# lidar4_sch.net
KiCad netlist of a schematic drawn in Altium Designer
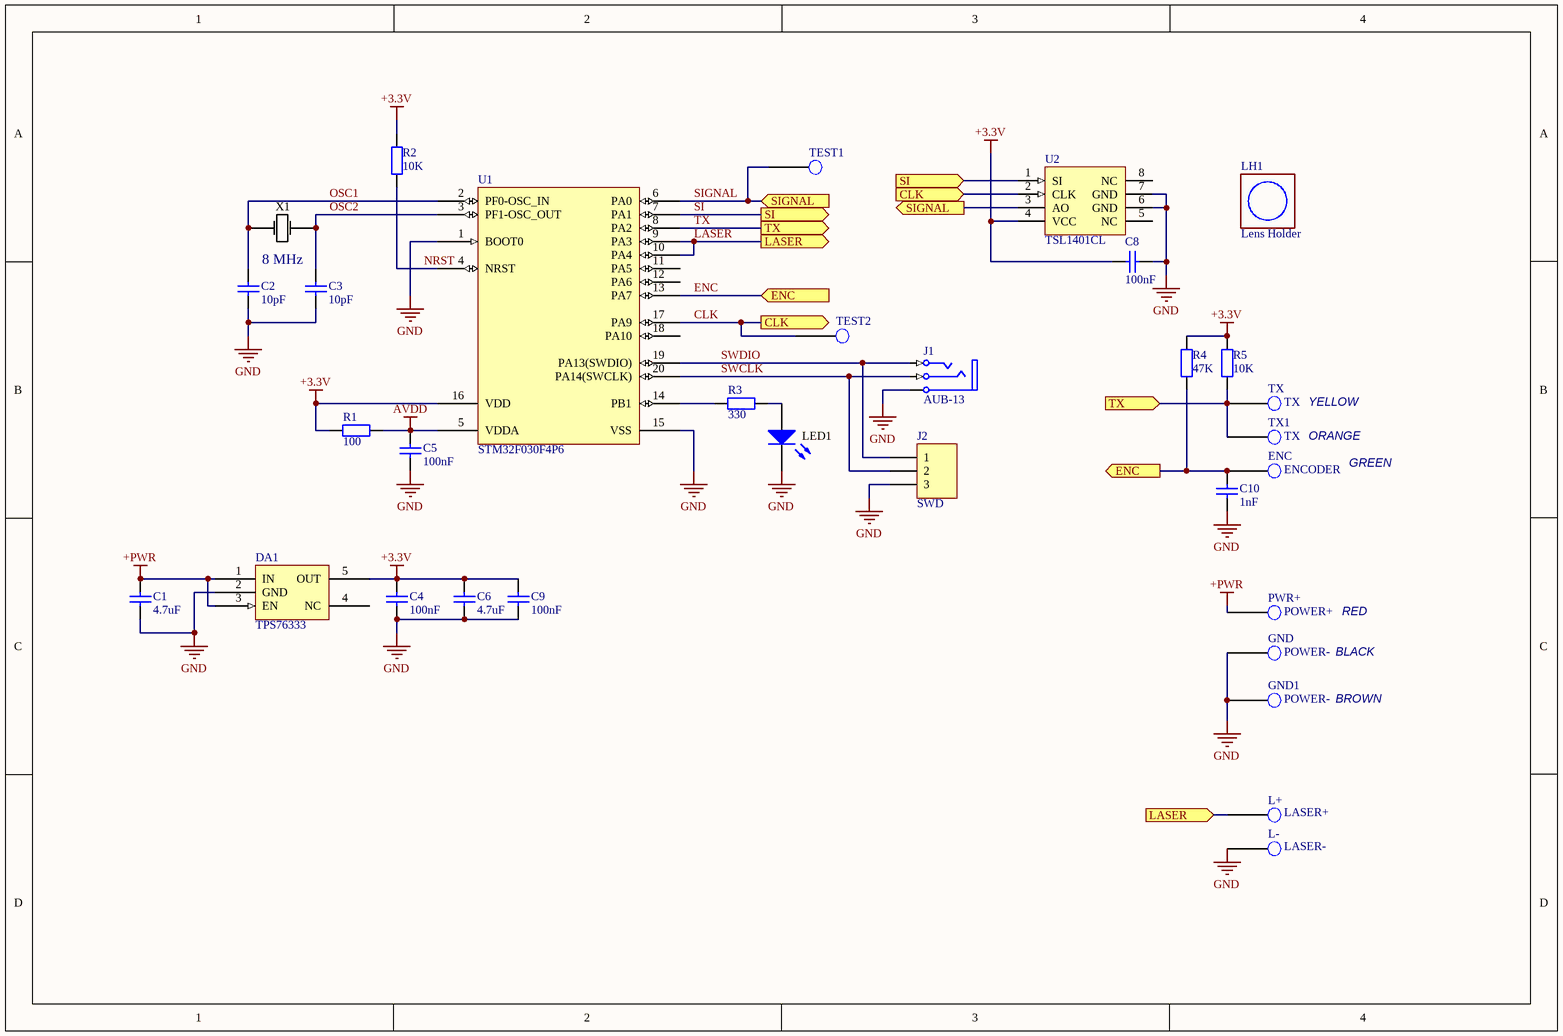
[diagram p0: lidar4_sch.SchDoc]

(export (version "E")
  (design (tool "Eeschema 10.0.6"))
  (components
    (comp (ref "C1")
      (value "4.7uF")
      (footprint "CAPC2012X135N")
      (description "Chip capacitor")
      (fields (field (name "VOLTAGE") "25V"))
      (libsource (lib "MyLibSch") (part "CC0805"))
    )
    (comp (ref "C2")
      (value "10pF")
      (footprint "CAPC1608X90N")
      (description "Chip capacitor")
      (fields (field (name "VOLTAGE") "25V"))
      (libsource (lib "MyLibSch") (part "CC0805"))
    )
    (comp (ref "C3")
      (value "10pF")
      (footprint "CAPC1608X90N")
      (description "Chip capacitor")
      (fields (field (name "VOLTAGE") "25V"))
      (libsource (lib "MyLibSch") (part "CC0805"))
    )
    (comp (ref "C4")
      (value "100nF")
      (footprint "CAPC1608X90N")
      (description "Chip capacitor")
      (fields (field (name "VOLTAGE") "25V"))
      (libsource (lib "MyLibSch") (part "CC0805"))
    )
    (comp (ref "C5")
      (value "100nF")
      (footprint "CAPC1608X90N")
      (description "Chip capacitor")
      (fields (field (name "VOLTAGE") "25V"))
      (libsource (lib "MyLibSch") (part "CC0805"))
    )
    (comp (ref "C6")
      (value "4.7uF")
      (footprint "CAPC2012X135N")
      (description "Chip capacitor")
      (fields (field (name "VOLTAGE") "25V"))
      (libsource (lib "MyLibSch") (part "CC0805"))
    )
    (comp (ref "C8")
      (value "100nF")
      (footprint "CAPC1608X90N")
      (description "Chip capacitor")
      (fields (field (name "VOLTAGE") "25V"))
      (libsource (lib "MyLibSch") (part "CC0805"))
    )
    (comp (ref "C9")
      (value "100nF")
      (footprint "CAPC1608X90N")
      (description "Chip capacitor")
      (fields (field (name "VOLTAGE") "25V"))
      (libsource (lib "MyLibSch") (part "CC0805"))
    )
    (comp (ref "C10")
      (value "1nF")
      (footprint "CAPC1608X90N")
      (description "Chip capacitor")
      (fields (field (name "VOLTAGE") "25V"))
      (libsource (lib "MyLibSch") (part "CC0805"))
    )
    (comp (ref "DA1")
      (value "TPS76333")
      (footprint "SOT23-5")
      (description "LDO")
      (libsource (lib "lcd_lib") (part "TPS76333"))
    )
    (comp (ref "ENC")
      (value "ENCODER")
      (footprint "Ext_hole")
      (description "Pad for wire")
      (libsource (lib "lcd_lib") (part "Ext Pad"))
    )
    (comp (ref "GND")
      (value "POWER-")
      (footprint "Ext_hole")
      (description "Pad for wire")
      (libsource (lib "lcd_lib") (part "Ext Pad"))
    )
    (comp (ref "GND1")
      (value "POWER-")
      (footprint "Ext_hole")
      (description "Pad for wire")
      (libsource (lib "lcd_lib") (part "Ext Pad"))
    )
    (comp (ref "J1")
      (value "AUB-13")
      (footprint "AUB-13")
      (description "Jack Socket, 1/4\" [6.5mm], Thru-Hole, Vertical, 3-Conductor Open Circuit (Non-Normalling)")
      (fields (field (name "PUBLISHER") "Altium Limited"))
      (libsource (lib "Miscellaneous Connectors") (part "Phonejack3"))
    )
    (comp (ref "J2")
      (value "SWD")
      (footprint "HDR1X3")
      (description "Header, 3-Pin")
      (fields (field (name "PUBLISHER") "Altium Limited"))
      (libsource (lib "Miscellaneous Connectors") (part "Header 3"))
    )
    (comp (ref "L+")
      (value "LASER+")
      (footprint "Ext_hole")
      (description "Pad for wire")
      (libsource (lib "lcd_lib") (part "Ext Pad"))
    )
    (comp (ref "L-")
      (value "LASER-")
      (footprint "Ext_hole")
      (description "Pad for wire")
      (libsource (lib "lcd_lib") (part "Ext Pad"))
    )
    (comp (ref "LED1")
      (value "LED")
      (footprint "PcbLib3:LED_0603")
      (description "LED_0603")
      (libsource (lib "lcd_lib") (part "LED_0603"))
    )
    (comp (ref "LH1")
      (value "Lens Holder")
      (footprint "LENS_HOLDER_2")
      (description "M12 Lens Holder")
      (libsource (lib "lcd_lib") (part "M12 Lens Holder"))
    )
    (comp (ref "PWR+")
      (value "POWER+")
      (footprint "Ext_hole")
      (description "Pad for wire")
      (libsource (lib "lcd_lib") (part "Ext Pad"))
    )
    (comp (ref "R1")
      (value "100")
      (footprint "RESC1608X55N")
      (description "Chip resistor")
      (fields (field (name "TOLERANCE") "5%"))
      (libsource (lib "") (part "RC0805_1"))
    )
    (comp (ref "R2")
      (value "10K")
      (footprint "RESC1608X55N")
      (description "Chip resistor")
      (fields (field (name "TOLERANCE") "5%"))
      (libsource (lib "MyLibSch") (part "RC0805"))
    )
    (comp (ref "R3")
      (value "330")
      (footprint "RESC1608X55N")
      (description "Chip resistor")
      (fields (field (name "TOLERANCE") "5%"))
      (libsource (lib "") (part "RC0805_2"))
    )
    (comp (ref "R4")
      (value "47K")
      (footprint "RESC1608X55N")
      (description "Chip resistor")
      (fields (field (name "TOLERANCE") "5%"))
      (libsource (lib "MyLibSch") (part "RC0805"))
    )
    (comp (ref "R5")
      (value "10K")
      (footprint "RESC1608X55N")
      (description "Chip resistor")
      (fields (field (name "TOLERANCE") "5%"))
      (libsource (lib "MyLibSch") (part "RC0805"))
    )
    (comp (ref "TEST1")
      (value "Pad")
      (footprint "PcbLib3:Ext_pad")
      (description "Pad for wire")
      (libsource (lib "lcd_lib") (part "Ext Pad"))
    )
    (comp (ref "TEST2")
      (value "Pad")
      (footprint "PcbLib3:Ext_pad")
      (description "Pad for wire")
      (libsource (lib "lcd_lib") (part "Ext Pad"))
    )
    (comp (ref "TX")
      (value "TX")
      (footprint "Ext_hole")
      (description "Pad for wire")
      (libsource (lib "lcd_lib") (part "Ext Pad"))
    )
    (comp (ref "TX1")
      (value "TX")
      (footprint "Ext_hole")
      (description "Pad for wire")
      (libsource (lib "lcd_lib") (part "Ext Pad"))
    )
    (comp (ref "U1")
      (value "STM32F030F4P6")
      (footprint "TSSOP65P640X120-20N")
      (libsource (lib "STM32 MCU") (part "STM32F030F4P6"))
    )
    (comp (ref "U2")
      (value "TSL1401CL")
      (footprint "PcbLib3:TSL1401CL_2")
      (description "Light sensor")
      (libsource (lib "lcd_lib") (part "TSL1401CL"))
    )
    (comp (ref "X1")
      (value "8 MHz")
      (footprint "SX-6 QUARTZ")
      (description "Quartz_SX-6 (SMD06035C4)")
      (fields (field (name "Comment") "Quartz"))
      (libsource (lib "lcd_lib") (part "Quartz_SX-6"))
    )
  )
  (nets
    (net (code "1") (name "+3.3V") (class "Default")
      (node (ref "C4") (pin "2") (pinfunction "2_2") (pintype "passive"))
      (node (ref "C6") (pin "2") (pinfunction "2_2") (pintype "passive"))
      (node (ref "C8") (pin "2") (pinfunction "2_2") (pintype "passive"))
      (node (ref "C9") (pin "2") (pinfunction "2_2") (pintype "passive"))
      (node (ref "DA1") (pin "5") (pinfunction "OUT_5") (pintype "passive"))
      (node (ref "R1") (pin "1") (pinfunction "1_1") (pintype "passive"))
      (node (ref "R2") (pin "1") (pinfunction "1_1") (pintype "passive"))
      (node (ref "R4") (pin "1") (pinfunction "1_1") (pintype "passive"))
      (node (ref "R5") (pin "1") (pinfunction "1_1") (pintype "passive"))
      (node (ref "U1") (pin "16") (pinfunction "VDD_16") (pintype "power_in"))
      (node (ref "U2") (pin "4") (pinfunction "VCC_4") (pintype "power_in"))
    )
    (net (code "2") (name "+PWR") (class "Default")
      (node (ref "C1") (pin "2") (pinfunction "2_2") (pintype "passive"))
      (node (ref "DA1") (pin "1") (pinfunction "IN_1") (pintype "power_in"))
      (node (ref "DA1") (pin "3") (pinfunction "EN_3") (pintype "input"))
      (node (ref "PWR+") (pin "1") (pinfunction "Pad_1") (pintype "passive"))
    )
    (net (code "3") (name "/CLK") (class "Default")
      (node (ref "TEST2") (pin "1") (pinfunction "Pad_1") (pintype "passive"))
      (node (ref "U1") (pin "17") (pinfunction "PA9_17") (pintype "bidirectional"))
      (node (ref "U2") (pin "2") (pinfunction "CLK_2") (pintype "input"))
    )
    (net (code "4") (name "/ENC") (class "Default")
      (node (ref "C10") (pin "2") (pinfunction "2_2") (pintype "passive"))
      (node (ref "ENC") (pin "1") (pinfunction "Pad_1") (pintype "passive"))
      (node (ref "R4") (pin "2") (pinfunction "2_2") (pintype "passive"))
      (node (ref "U1") (pin "13") (pinfunction "PA7_13") (pintype "bidirectional"))
    )
    (net (code "5") (name "/LASER") (class "Default")
      (node (ref "L+") (pin "1") (pinfunction "Pad_1") (pintype "passive"))
      (node (ref "U1") (pin "10") (pinfunction "PA4_10") (pintype "bidirectional"))
      (node (ref "U1") (pin "9") (pinfunction "PA3_9") (pintype "bidirectional"))
    )
    (net (code "6") (name "/NRST") (class "Default")
      (node (ref "R2") (pin "2") (pinfunction "2_2") (pintype "passive"))
      (node (ref "U1") (pin "4") (pinfunction "NRST_4") (pintype "bidirectional"))
    )
    (net (code "7") (name "/OSC1") (class "Default")
      (node (ref "C2") (pin "2") (pinfunction "2_2") (pintype "passive"))
      (node (ref "U1") (pin "2") (pinfunction "PF0-OSC_IN_2") (pintype "bidirectional"))
      (node (ref "X1") (pin "1") (pinfunction "1_1") (pintype "passive"))
    )
    (net (code "8") (name "/OSC2") (class "Default")
      (node (ref "C3") (pin "2") (pinfunction "2_2") (pintype "passive"))
      (node (ref "U1") (pin "3") (pinfunction "PF1-OSC_OUT_3") (pintype "bidirectional"))
      (node (ref "X1") (pin "3") (pinfunction "3_3") (pintype "passive"))
    )
    (net (code "9") (name "/SI") (class "Default")
      (node (ref "U1") (pin "7") (pinfunction "PA1_7") (pintype "bidirectional"))
      (node (ref "U2") (pin "1") (pinfunction "SI_1") (pintype "input"))
    )
    (net (code "10") (name "/SIGNAL") (class "Default")
      (node (ref "TEST1") (pin "1") (pinfunction "Pad_1") (pintype "passive"))
      (node (ref "U1") (pin "6") (pinfunction "PA0_6") (pintype "bidirectional"))
      (node (ref "U2") (pin "3") (pinfunction "AO_3") (pintype "passive"))
    )
    (net (code "11") (name "/SWCLK") (class "Default")
      (node (ref "J1") (pin "3") (pinfunction "R_3") (pintype "input"))
      (node (ref "J2") (pin "2") (pinfunction "2_2") (pintype "passive"))
      (node (ref "U1") (pin "20") (pinfunction "PA14(SWCLK)_20") (pintype "bidirectional"))
    )
    (net (code "12") (name "/SWDIO") (class "Default")
      (node (ref "J1") (pin "1") (pinfunction "T_1") (pintype "input"))
      (node (ref "J2") (pin "1") (pinfunction "1_1") (pintype "passive"))
      (node (ref "U1") (pin "19") (pinfunction "PA13(SWDIO)_19") (pintype "bidirectional"))
    )
    (net (code "13") (name "/TX") (class "Default")
      (node (ref "R5") (pin "2") (pinfunction "2_2") (pintype "passive"))
      (node (ref "TX") (pin "1") (pinfunction "Pad_1") (pintype "passive"))
      (node (ref "TX1") (pin "1") (pinfunction "Pad_1") (pintype "passive"))
      (node (ref "U1") (pin "8") (pinfunction "PA2_8") (pintype "bidirectional"))
    )
    (net (code "14") (name "AVDD") (class "Default")
      (node (ref "C5") (pin "2") (pinfunction "2_2") (pintype "passive"))
      (node (ref "R1") (pin "2") (pinfunction "2_2") (pintype "passive"))
      (node (ref "U1") (pin "5") (pinfunction "VDDA_5") (pintype "power_in"))
    )
    (net (code "15") (name "GND") (class "Default")
      (node (ref "C1") (pin "1") (pinfunction "1_1") (pintype "passive"))
      (node (ref "C10") (pin "1") (pinfunction "1_1") (pintype "passive"))
      (node (ref "C2") (pin "1") (pinfunction "1_1") (pintype "passive"))
      (node (ref "C3") (pin "1") (pinfunction "1_1") (pintype "passive"))
      (node (ref "C4") (pin "1") (pinfunction "1_1") (pintype "passive"))
      (node (ref "C5") (pin "1") (pinfunction "1_1") (pintype "passive"))
      (node (ref "C6") (pin "1") (pinfunction "1_1") (pintype "passive"))
      (node (ref "C8") (pin "1") (pinfunction "1_1") (pintype "passive"))
      (node (ref "C9") (pin "1") (pinfunction "1_1") (pintype "passive"))
      (node (ref "DA1") (pin "2") (pinfunction "GND_2") (pintype "power_in"))
      (node (ref "GND") (pin "1") (pinfunction "Pad_1") (pintype "passive"))
      (node (ref "GND1") (pin "1") (pinfunction "Pad_1") (pintype "passive"))
      (node (ref "J1") (pin "5") (pinfunction "S_5") (pintype "power_in"))
      (node (ref "J2") (pin "3") (pinfunction "3_3") (pintype "passive"))
      (node (ref "L-") (pin "1") (pinfunction "Pad_1") (pintype "passive"))
      (node (ref "LED1") (pin "2") (pinfunction "K_2") (pintype "passive"))
      (node (ref "U1") (pin "1") (pinfunction "BOOT0_1") (pintype "input"))
      (node (ref "U1") (pin "15") (pinfunction "VSS_15") (pintype "power_in"))
      (node (ref "U2") (pin "6") (pinfunction "GND_6") (pintype "power_in"))
      (node (ref "U2") (pin "7") (pinfunction "GND_7") (pintype "power_in"))
    )
    (net (code "16") (name "Net-(LED1-A)") (class "Default")
      (node (ref "LED1") (pin "1") (pinfunction "A_1") (pintype "passive"))
      (node (ref "R3") (pin "1") (pinfunction "1_1") (pintype "passive"))
    )
    (net (code "17") (name "Net-(U1-PB1)") (class "Default")
      (node (ref "R3") (pin "2") (pinfunction "2_2") (pintype "passive"))
      (node (ref "U1") (pin "14") (pinfunction "PB1_14") (pintype "bidirectional"))
    )
    (net (code "18") (name "unconnected-(DA1-NC-Pad4)") (class "Default")
      (node (ref "DA1") (pin "4") (pinfunction "NC_4") (pintype "passive"))
    )
    (net (code "19") (name "unconnected-(U1-PA5-Pad11)") (class "Default")
      (node (ref "U1") (pin "11") (pinfunction "PA5_11") (pintype "bidirectional"))
    )
    (net (code "20") (name "unconnected-(U1-PA6-Pad12)") (class "Default")
      (node (ref "U1") (pin "12") (pinfunction "PA6_12") (pintype "bidirectional"))
    )
    (net (code "21") (name "unconnected-(U1-PA10-Pad18)") (class "Default")
      (node (ref "U1") (pin "18") (pinfunction "PA10_18") (pintype "bidirectional"))
    )
    (net (code "22") (name "unconnected-(U2-NC-Pad5)") (class "Default")
      (node (ref "U2") (pin "5") (pinfunction "NC_5") (pintype "passive"))
    )
    (net (code "23") (name "unconnected-(U2-NC-Pad8)") (class "Default")
      (node (ref "U2") (pin "8") (pinfunction "NC_8") (pintype "passive"))
    )
  )
)
